# Sheet_PIC.net
KiCad netlist of a schematic drawn in Altium Designer
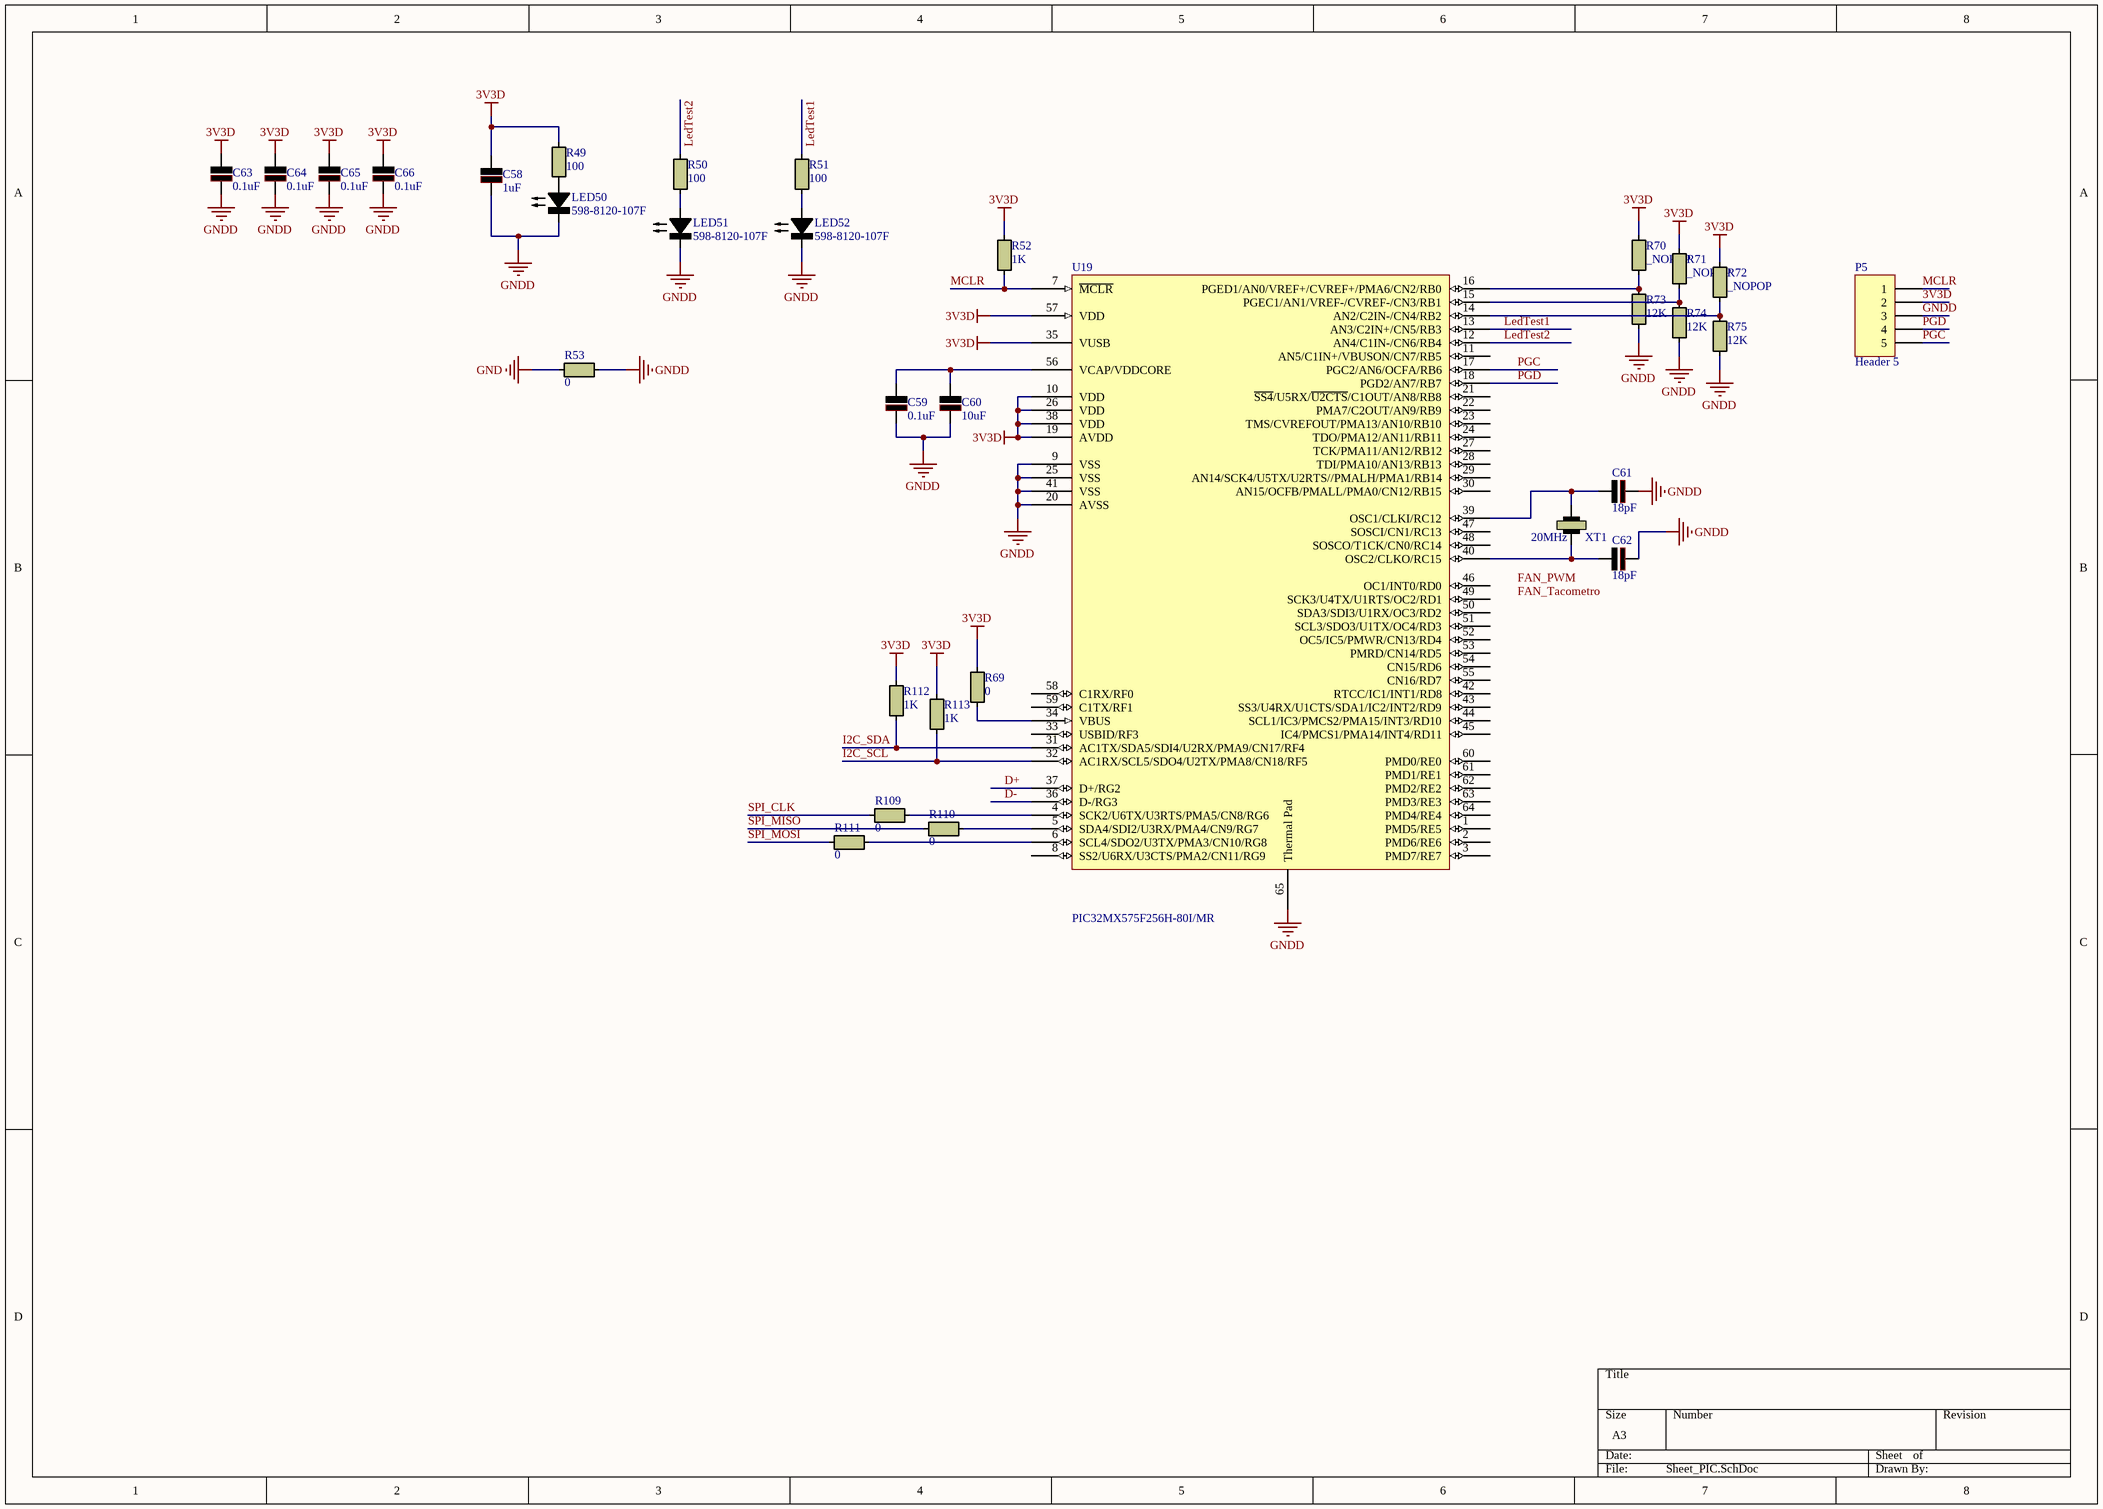
[diagram p0: Sheet_PIC.SchDoc]

(export (version "E")
  (design (tool "Eeschema 10.0.6"))
  (components
    (comp (ref "C58") (value "1uF") (footprint "C_0805") (libsource (lib "Alberto_Sch") (part "C")))
    (comp (ref "C59") (value "0.1uF") (footprint "C_0402") (libsource (lib "Alberto_Sch") (part "C")))
    (comp (ref "C60") (value "10uF") (footprint "C_0805") (libsource (lib "Alberto_Sch") (part "C")))
    (comp (ref "C61") (value "18pF") (footprint "C_0402") (libsource (lib "") (part "C_1")))
    (comp (ref "C62") (value "18pF") (footprint "C_0402") (libsource (lib "") (part "C_1")))
    (comp (ref "C63") (value "0.1uF") (footprint "C_0402") (libsource (lib "Alberto_Sch") (part "C")))
    (comp (ref "C64") (value "0.1uF") (footprint "C_0402") (libsource (lib "Alberto_Sch") (part "C")))
    (comp (ref "C65") (value "0.1uF") (footprint "C_0402") (libsource (lib "Alberto_Sch") (part "C")))
    (comp (ref "C66") (value "0.1uF") (footprint "C_0402") (libsource (lib "Alberto_Sch") (part "C")))
    (comp (ref "LED50")
      (value "598-8120-107F")
      (footprint "LED_0805")
      (libsource (lib "Alberto_Sch") (part "LED"))
    )
    (comp (ref "LED51")
      (value "598-8120-107F")
      (footprint "LED_0805")
      (libsource (lib "Alberto_Sch") (part "LED"))
    )
    (comp (ref "LED52")
      (value "598-8120-107F")
      (footprint "LED_0805")
      (libsource (lib "Alberto_Sch") (part "LED"))
    )
    (comp (ref "P5")
      (value "Header 5")
      (footprint "header5_molex_53398_1.25_vertical")
      (description "Header, 5-Pin")
      (fields (field (name "PUBLISHER") "Altium Limited"))
      (libsource (lib "Miscellaneous Connectors") (part "Header 5"))
    )
    (comp (ref "R49") (value "100") (footprint "R_0402") (libsource (lib "Alberto_Sch") (part "R")))
    (comp (ref "R50") (value "100") (footprint "R_0402") (libsource (lib "Alberto_Sch") (part "R")))
    (comp (ref "R51") (value "100") (footprint "R_0402") (libsource (lib "Alberto_Sch") (part "R")))
    (comp (ref "R52") (value "1K") (footprint "R_0402") (libsource (lib "") (part "R_2")))
    (comp (ref "R53") (value "0") (footprint "R_0805") (libsource (lib "") (part "R_1")))
    (comp (ref "R69") (value "0") (footprint "R_0402") (libsource (lib "Alberto_Sch") (part "R")))
    (comp (ref "R70") (value "_NOPOP") (footprint "R_0402") (libsource (lib "") (part "R_2")))
    (comp (ref "R71") (value "_NOPOP") (footprint "R_0402") (libsource (lib "") (part "R_2")))
    (comp (ref "R72") (value "_NOPOP") (footprint "R_0402") (libsource (lib "") (part "R_2")))
    (comp (ref "R73") (value "12K") (footprint "R_0402") (libsource (lib "") (part "R_2")))
    (comp (ref "R74") (value "12K") (footprint "R_0402") (libsource (lib "") (part "R_2")))
    (comp (ref "R75") (value "12K") (footprint "R_0402") (libsource (lib "") (part "R_2")))
    (comp (ref "R109") (value "0") (footprint "R_0402") (libsource (lib "") (part "R_1")))
    (comp (ref "R110") (value "0") (footprint "R_0402") (libsource (lib "") (part "R_1")))
    (comp (ref "R111") (value "0") (footprint "R_0402") (libsource (lib "") (part "R_1")))
    (comp (ref "R112") (value "1K") (footprint "R_0402") (libsource (lib "Alberto_Sch") (part "R")))
    (comp (ref "R113") (value "1K") (footprint "R_0402") (libsource (lib "Alberto_Sch") (part "R")))
    (comp (ref "U19")
      (value "PIC32MX575F256H-80I/MR")
      (libsource (lib "Alberto_Sch") (part "PIC32MX575F256H-80I/PT"))
    )
    (comp (ref "XT1") (value "20MHz") (footprint "XTAL_ABM7") (libsource (lib "Alberto_Sch") (part "XTAL")))
  )
  (nets
    (net (code "1") (name "/D+") (class "Default")
      (node (ref "U19") (pin "37") (pinfunction "D+/RG2_37") (pintype "bidirectional"))
    )
    (net (code "2") (name "/D-") (class "Default")
      (node (ref "U19") (pin "36") (pinfunction "D-/RG3_36") (pintype "bidirectional"))
    )
    (net (code "5") (name "/I2C_SCL") (class "Default")
      (node (ref "R113") (pin "1") (pintype "passive"))
      (node (ref "U19") (pin "32") (pinfunction "AC1RX/SCL5/SDO4/U2TX/PMA8/CN18/RF5_32") (pintype "bidirectional"))
    )
    (net (code "6") (name "/I2C_SDA") (class "Default")
      (node (ref "R112") (pin "1") (pintype "passive"))
      (node (ref "U19") (pin "31") (pinfunction "AC1TX/SDA5/SDI4/U2RX/PMA9/CN17/RF4_31") (pintype "bidirectional"))
    )
    (net (code "7") (name "/LedTest1") (class "Default")
      (node (ref "R51") (pin "2") (pintype "passive"))
      (node (ref "U19") (pin "13") (pinfunction "AN3/C2IN+/CN5/RB3_13") (pintype "bidirectional"))
    )
    (net (code "8") (name "/LedTest2") (class "Default")
      (node (ref "R50") (pin "2") (pintype "passive"))
      (node (ref "U19") (pin "12") (pinfunction "AN4/C1IN-/CN6/RB4_12") (pintype "bidirectional"))
    )
    (net (code "9") (name "/MCLR") (class "Default")
      (node (ref "P5") (pin "1") (pinfunction "1_1") (pintype "passive"))
      (node (ref "R52") (pin "2") (pintype "passive"))
      (node (ref "U19") (pin "7") (pinfunction "~{MCLR}_7") (pintype "input"))
    )
    (net (code "10") (name "/PGC") (class "Default")
      (node (ref "P5") (pin "5") (pinfunction "5_5") (pintype "passive"))
      (node (ref "U19") (pin "17") (pinfunction "PGC2/AN6/OCFA/RB6_17") (pintype "bidirectional"))
    )
    (net (code "11") (name "/PGD") (class "Default")
      (node (ref "P5") (pin "4") (pinfunction "4_4") (pintype "passive"))
      (node (ref "U19") (pin "18") (pinfunction "PGD2/AN7/RB7_18") (pintype "bidirectional"))
    )
    (net (code "12") (name "/SPI_CLK") (class "Default") (node (ref "R109") (pin "1") (pintype "passive")))
    (net (code "13") (name "/SPI_MISO") (class "Default") (node (ref "R110") (pin "1") (pintype "passive")))
    (net (code "14") (name "/SPI_MOSI") (class "Default") (node (ref "R111") (pin "1") (pintype "passive")))
    (net (code "15") (name "3V3D") (class "Default")
      (node (ref "C58") (pin "1") (pintype "passive"))
      (node (ref "C63") (pin "1") (pintype "passive"))
      (node (ref "C64") (pin "1") (pintype "passive"))
      (node (ref "C65") (pin "1") (pintype "passive"))
      (node (ref "C66") (pin "1") (pintype "passive"))
      (node (ref "P5") (pin "2") (pinfunction "2_2") (pintype "passive"))
      (node (ref "R112") (pin "2") (pintype "passive"))
      (node (ref "R113") (pin "2") (pintype "passive"))
      (node (ref "R49") (pin "2") (pintype "passive"))
      (node (ref "R52") (pin "1") (pintype "passive"))
      (node (ref "R69") (pin "2") (pintype "passive"))
      (node (ref "R70") (pin "1") (pintype "passive"))
      (node (ref "R71") (pin "1") (pintype "passive"))
      (node (ref "R72") (pin "1") (pintype "passive"))
      (node (ref "U19") (pin "10") (pinfunction "VDD_10") (pintype "power_in"))
      (node (ref "U19") (pin "19") (pinfunction "AVDD_19") (pintype "power_in"))
      (node (ref "U19") (pin "26") (pinfunction "VDD_26") (pintype "power_in"))
      (node (ref "U19") (pin "35") (pinfunction "VUSB_35") (pintype "power_in"))
      (node (ref "U19") (pin "38") (pinfunction "VDD_38") (pintype "power_in"))
      (node (ref "U19") (pin "57") (pinfunction "VDD_57") (pintype "input"))
    )
    (net (code "16") (name "GND") (class "Default") (node (ref "R53") (pin "1") (pintype "passive")))
    (net (code "17") (name "GNDD") (class "Default")
      (node (ref "C58") (pin "2") (pintype "passive"))
      (node (ref "C59") (pin "2") (pintype "passive"))
      (node (ref "C60") (pin "2") (pintype "passive"))
      (node (ref "C61") (pin "2") (pintype "passive"))
      (node (ref "C62") (pin "2") (pintype "passive"))
      (node (ref "C63") (pin "2") (pintype "passive"))
      (node (ref "C64") (pin "2") (pintype "passive"))
      (node (ref "C65") (pin "2") (pintype "passive"))
      (node (ref "C66") (pin "2") (pintype "passive"))
      (node (ref "LED50") (pin "K") (pintype "passive"))
      (node (ref "LED51") (pin "K") (pintype "passive"))
      (node (ref "LED52") (pin "K") (pintype "passive"))
      (node (ref "P5") (pin "3") (pinfunction "3_3") (pintype "passive"))
      (node (ref "R53") (pin "2") (pintype "passive"))
      (node (ref "R73") (pin "2") (pintype "passive"))
      (node (ref "R74") (pin "2") (pintype "passive"))
      (node (ref "R75") (pin "2") (pintype "passive"))
      (node (ref "U19") (pin "20") (pinfunction "AVSS_20") (pintype "power_in"))
      (node (ref "U19") (pin "25") (pinfunction "VSS_25") (pintype "power_in"))
      (node (ref "U19") (pin "41") (pinfunction "VSS_41") (pintype "power_in"))
      (node (ref "U19") (pin "65") (pinfunction "Thermal_Pad_65") (pintype "passive"))
      (node (ref "U19") (pin "9") (pinfunction "VSS_9") (pintype "power_in"))
    )
    (net (code "18") (name "Net-(LED50-PadA)") (class "Default")
      (node (ref "LED50") (pin "A") (pintype "passive"))
      (node (ref "R49") (pin "1") (pintype "passive"))
    )
    (net (code "19") (name "Net-(LED51-PadA)") (class "Default")
      (node (ref "LED51") (pin "A") (pintype "passive"))
      (node (ref "R50") (pin "1") (pintype "passive"))
    )
    (net (code "20") (name "Net-(LED52-PadA)") (class "Default")
      (node (ref "LED52") (pin "A") (pintype "passive"))
      (node (ref "R51") (pin "1") (pintype "passive"))
    )
    (net (code "21") (name "Net-(U19-AN2{slash}C2IN-{slash}CN4{slash}RB2)") (class "Default")
      (node (ref "R72") (pin "2") (pintype "passive"))
      (node (ref "R75") (pin "1") (pintype "passive"))
      (node (ref "U19") (pin "14") (pinfunction "AN2/C2IN-/CN4/RB2_14") (pintype "bidirectional"))
    )
    (net (code "22") (name "Net-(U19-OSC1{slash}CLKI{slash}RC12)") (class "Default")
      (node (ref "C61") (pin "1") (pintype "passive"))
      (node (ref "U19") (pin "39") (pinfunction "OSC1/CLKI/RC12_39") (pintype "bidirectional"))
      (node (ref "XT1") (pin "2") (pintype "passive"))
    )
    (net (code "23") (name "Net-(U19-OSC2{slash}CLKO{slash}RC15)") (class "Default")
      (node (ref "C62") (pin "1") (pintype "passive"))
      (node (ref "U19") (pin "40") (pinfunction "OSC2/CLKO/RC15_40") (pintype "bidirectional"))
      (node (ref "XT1") (pin "1") (pintype "passive"))
    )
    (net (code "24") (name "Net-(U19-PGEC1{slash}AN1{slash}VREF-{slash}CVREF-{slash}CN3{slash}RB1)") (class "Default")
      (node (ref "R71") (pin "2") (pintype "passive"))
      (node (ref "R74") (pin "1") (pintype "passive"))
      (node (ref "U19") (pin "15") (pinfunction "PGEC1/AN1/VREF-/CVREF-/CN3/RB1_15") (pintype "bidirectional"))
    )
    (net (code "25") (name "Net-(U19-PGED1{slash}AN0{slash}VREF+{slash}CVREF+{slash}PMA6{slash}CN2{slash}RB0)") (class "Default")
      (node (ref "R70") (pin "2") (pintype "passive"))
      (node (ref "R73") (pin "1") (pintype "passive"))
      (node (ref "U19") (pin "16") (pinfunction "PGED1/AN0/VREF+/CVREF+/PMA6/CN2/RB0_16") (pintype "bidirectional"))
    )
    (net (code "26") (name "Net-(U19-SCK2{slash}U6TX{slash}U3RTS{slash}PMA5{slash}CN8{slash}RG6)") (class "Default")
      (node (ref "R109") (pin "2") (pintype "passive"))
      (node (ref "U19") (pin "4") (pinfunction "SCK2/U6TX/U3RTS/PMA5/CN8/RG6_4") (pintype "bidirectional"))
    )
    (net (code "27") (name "Net-(U19-SCL4{slash}SDO2{slash}U3TX{slash}PMA3{slash}CN10{slash}RG8)") (class "Default")
      (node (ref "R111") (pin "2") (pintype "passive"))
      (node (ref "U19") (pin "6") (pinfunction "SCL4/SDO2/U3TX/PMA3/CN10/RG8_6") (pintype "bidirectional"))
    )
    (net (code "28") (name "Net-(U19-SDA4{slash}SDI2{slash}U3RX{slash}PMA4{slash}CN9{slash}RG7)") (class "Default")
      (node (ref "R110") (pin "2") (pintype "passive"))
      (node (ref "U19") (pin "5") (pinfunction "SDA4/SDI2/U3RX/PMA4/CN9/RG7_5") (pintype "bidirectional"))
    )
    (net (code "29") (name "Net-(U19-VBUS)") (class "Default")
      (node (ref "R69") (pin "1") (pintype "passive"))
      (node (ref "U19") (pin "34") (pinfunction "VBUS_34") (pintype "input"))
    )
    (net (code "30") (name "Net-(U19-VCAP{slash}VDDCORE)") (class "Default")
      (node (ref "C59") (pin "1") (pintype "passive"))
      (node (ref "C60") (pin "1") (pintype "passive"))
      (node (ref "U19") (pin "56") (pinfunction "VCAP/VDDCORE_56") (pintype "power_in"))
    )
    (net (code "31") (name "unconnected-(U19-AN5{slash}C1IN+{slash}VBUSON{slash}CN7{slash}RB5-Pad11)") (class "Default")
      (node (ref "U19") (pin "11") (pinfunction "AN5/C1IN+/VBUSON/CN7/RB5_11") (pintype "bidirectional"))
    )
    (net (code "32") (name "unconnected-(U19-AN14{slash}SCK4{slash}U5TX{slash}U2RTS{slash}{slash}PMALH{slash}PMA1{slash}RB14-Pad29)") (class "Default")
      (node (ref "U19") (pin "29") (pinfunction "AN14/SCK4/U5TX/U2RTS//PMALH/PMA1/RB14_29") (pintype "bidirectional"))
    )
    (net (code "33") (name "unconnected-(U19-AN15{slash}OCFB{slash}PMALL{slash}PMA0{slash}CN12{slash}RB15-Pad30)") (class "Default")
      (node (ref "U19") (pin "30") (pinfunction "AN15/OCFB/PMALL/PMA0/CN12/RB15_30") (pintype "bidirectional"))
    )
    (net (code "34") (name "unconnected-(U19-C1RX{slash}RF0-Pad58)") (class "Default")
      (node (ref "U19") (pin "58") (pinfunction "C1RX/RF0_58") (pintype "bidirectional"))
    )
    (net (code "35") (name "unconnected-(U19-C1TX{slash}RF1-Pad59)") (class "Default")
      (node (ref "U19") (pin "59") (pinfunction "C1TX/RF1_59") (pintype "bidirectional"))
    )
    (net (code "36") (name "unconnected-(U19-CN15{slash}RD6-Pad54)") (class "Default")
      (node (ref "U19") (pin "54") (pinfunction "CN15/RD6_54") (pintype "bidirectional"))
    )
    (net (code "37") (name "unconnected-(U19-CN16{slash}RD7-Pad55)") (class "Default")
      (node (ref "U19") (pin "55") (pinfunction "CN16/RD7_55") (pintype "bidirectional"))
    )
    (net (code "38") (name "unconnected-(U19-IC4{slash}PMCS1{slash}PMA14{slash}INT4{slash}RD11-Pad45)") (class "Default")
      (node (ref "U19") (pin "45") (pinfunction "IC4/PMCS1/PMA14/INT4/RD11_45") (pintype "bidirectional"))
    )
    (net (code "39") (name "unconnected-(U19-OC1{slash}INT0{slash}RD0-Pad46)") (class "Default")
      (node (ref "U19") (pin "46") (pinfunction "OC1/INT0/RD0_46") (pintype "bidirectional"))
    )
    (net (code "40") (name "unconnected-(U19-OC5{slash}IC5{slash}PMWR{slash}CN13{slash}RD4-Pad52)") (class "Default")
      (node (ref "U19") (pin "52") (pinfunction "OC5/IC5/PMWR/CN13/RD4_52") (pintype "bidirectional"))
    )
    (net (code "41") (name "unconnected-(U19-PMA7{slash}C2OUT{slash}AN9{slash}RB9-Pad22)") (class "Default")
      (node (ref "U19") (pin "22") (pinfunction "PMA7/C2OUT/AN9/RB9_22") (pintype "bidirectional"))
    )
    (net (code "42") (name "unconnected-(U19-PMD0{slash}RE0-Pad60)") (class "Default")
      (node (ref "U19") (pin "60") (pinfunction "PMD0/RE0_60") (pintype "bidirectional"))
    )
    (net (code "43") (name "unconnected-(U19-PMD1{slash}RE1-Pad61)") (class "Default")
      (node (ref "U19") (pin "61") (pinfunction "PMD1/RE1_61") (pintype "bidirectional"))
    )
    (net (code "44") (name "unconnected-(U19-PMD2{slash}RE2-Pad62)") (class "Default")
      (node (ref "U19") (pin "62") (pinfunction "PMD2/RE2_62") (pintype "bidirectional"))
    )
    (net (code "45") (name "unconnected-(U19-PMD3{slash}RE3-Pad63)") (class "Default")
      (node (ref "U19") (pin "63") (pinfunction "PMD3/RE3_63") (pintype "bidirectional"))
    )
    (net (code "46") (name "unconnected-(U19-PMD4{slash}RE4-Pad64)") (class "Default")
      (node (ref "U19") (pin "64") (pinfunction "PMD4/RE4_64") (pintype "bidirectional"))
    )
    (net (code "47") (name "unconnected-(U19-PMD5{slash}RE5-Pad1)") (class "Default")
      (node (ref "U19") (pin "1") (pinfunction "PMD5/RE5_1") (pintype "bidirectional"))
    )
    (net (code "48") (name "unconnected-(U19-PMD6{slash}RE6-Pad2)") (class "Default")
      (node (ref "U19") (pin "2") (pinfunction "PMD6/RE6_2") (pintype "bidirectional"))
    )
    (net (code "49") (name "unconnected-(U19-PMD7{slash}RE7-Pad3)") (class "Default")
      (node (ref "U19") (pin "3") (pinfunction "PMD7/RE7_3") (pintype "bidirectional"))
    )
    (net (code "50") (name "unconnected-(U19-PMRD{slash}CN14{slash}RD5-Pad53)") (class "Default")
      (node (ref "U19") (pin "53") (pinfunction "PMRD/CN14/RD5_53") (pintype "bidirectional"))
    )
    (net (code "51") (name "unconnected-(U19-RTCC{slash}IC1{slash}INT1{slash}RD8-Pad42)") (class "Default")
      (node (ref "U19") (pin "42") (pinfunction "RTCC/IC1/INT1/RD8_42") (pintype "bidirectional"))
    )
    (net (code "52") (name "unconnected-(U19-SCK3{slash}U4TX{slash}U1RTS{slash}OC2{slash}RD1-Pad49)") (class "Default")
      (node (ref "U19") (pin "49") (pinfunction "SCK3/U4TX/U1RTS/OC2/RD1_49") (pintype "bidirectional"))
    )
    (net (code "53") (name "unconnected-(U19-SCL1{slash}IC3{slash}PMCS2{slash}PMA15{slash}INT3{slash}RD10-Pad44)") (class "Default")
      (node (ref "U19") (pin "44") (pinfunction "SCL1/IC3/PMCS2/PMA15/INT3/RD10_44") (pintype "bidirectional"))
    )
    (net (code "54") (name "unconnected-(U19-SCL3{slash}SDO3{slash}U1TX{slash}OC4{slash}RD3-Pad51)") (class "Default")
      (node (ref "U19") (pin "51") (pinfunction "SCL3/SDO3/U1TX/OC4/RD3_51") (pintype "bidirectional"))
    )
    (net (code "55") (name "unconnected-(U19-SDA3{slash}SDI3{slash}U1RX{slash}OC3{slash}RD2-Pad50)") (class "Default")
      (node (ref "U19") (pin "50") (pinfunction "SDA3/SDI3/U1RX/OC3/RD2_50") (pintype "bidirectional"))
    )
    (net (code "56") (name "unconnected-(U19-SOSCI{slash}CN1{slash}RC13-Pad47)") (class "Default")
      (node (ref "U19") (pin "47") (pinfunction "SOSCI/CN1/RC13_47") (pintype "bidirectional"))
    )
    (net (code "57") (name "unconnected-(U19-SOSCO{slash}T1CK{slash}CN0{slash}RC14-Pad48)") (class "Default")
      (node (ref "U19") (pin "48") (pinfunction "SOSCO/T1CK/CN0/RC14_48") (pintype "bidirectional"))
    )
    (net (code "58") (name "unconnected-(U19-SS2{slash}U6RX{slash}U3CTS{slash}PMA2{slash}CN11{slash}RG9-Pad8)") (class "Default")
      (node (ref "U19") (pin "8") (pinfunction "SS2/U6RX/U3CTS/PMA2/CN11/RG9_8") (pintype "bidirectional"))
    )
    (net (code "59") (name "unconnected-(U19-SS3{slash}U4RX{slash}U1CTS{slash}SDA1{slash}IC2{slash}INT2{slash}RD9-Pad43)") (class "Default")
      (node (ref "U19") (pin "43") (pinfunction "SS3/U4RX/U1CTS/SDA1/IC2/INT2/RD9_43") (pintype "bidirectional"))
    )
    (net (code "60") (name "unconnected-(U19-TCK{slash}PMA11{slash}AN12{slash}RB12-Pad27)") (class "Default")
      (node (ref "U19") (pin "27") (pinfunction "TCK/PMA11/AN12/RB12_27") (pintype "bidirectional"))
    )
    (net (code "61") (name "unconnected-(U19-TDI{slash}PMA10{slash}AN13{slash}RB13-Pad28)") (class "Default")
      (node (ref "U19") (pin "28") (pinfunction "TDI/PMA10/AN13/RB13_28") (pintype "bidirectional"))
    )
    (net (code "62") (name "unconnected-(U19-TDO{slash}PMA12{slash}AN11{slash}RB11-Pad24)") (class "Default")
      (node (ref "U19") (pin "24") (pinfunction "TDO/PMA12/AN11/RB11_24") (pintype "bidirectional"))
    )
    (net (code "63") (name "unconnected-(U19-TMS{slash}CVREFOUT{slash}PMA13{slash}AN10{slash}RB10-Pad23)") (class "Default")
      (node (ref "U19") (pin "23") (pinfunction "TMS/CVREFOUT/PMA13/AN10/RB10_23") (pintype "bidirectional"))
    )
    (net (code "64") (name "unconnected-(U19-USBID{slash}RF3-Pad33)") (class "Default")
      (node (ref "U19") (pin "33") (pinfunction "USBID/RF3_33") (pintype "bidirectional"))
    )
    (net (code "65") (name "unconnected-(U19-~{SS4}{slash}U5RX{slash}~{U2CTS}{slash}C1OUT{slash}AN8{slash}RB8-Pad21)") (class "Default")
      (node (ref "U19") (pin "21") (pinfunction "~{SS4}/U5RX/~{U2CTS}/C1OUT/AN8/RB8_21") (pintype "bidirectional"))
    )
  )
)
